# FanController_v1.net
KiCad netlist of a schematic drawn in EAGLE
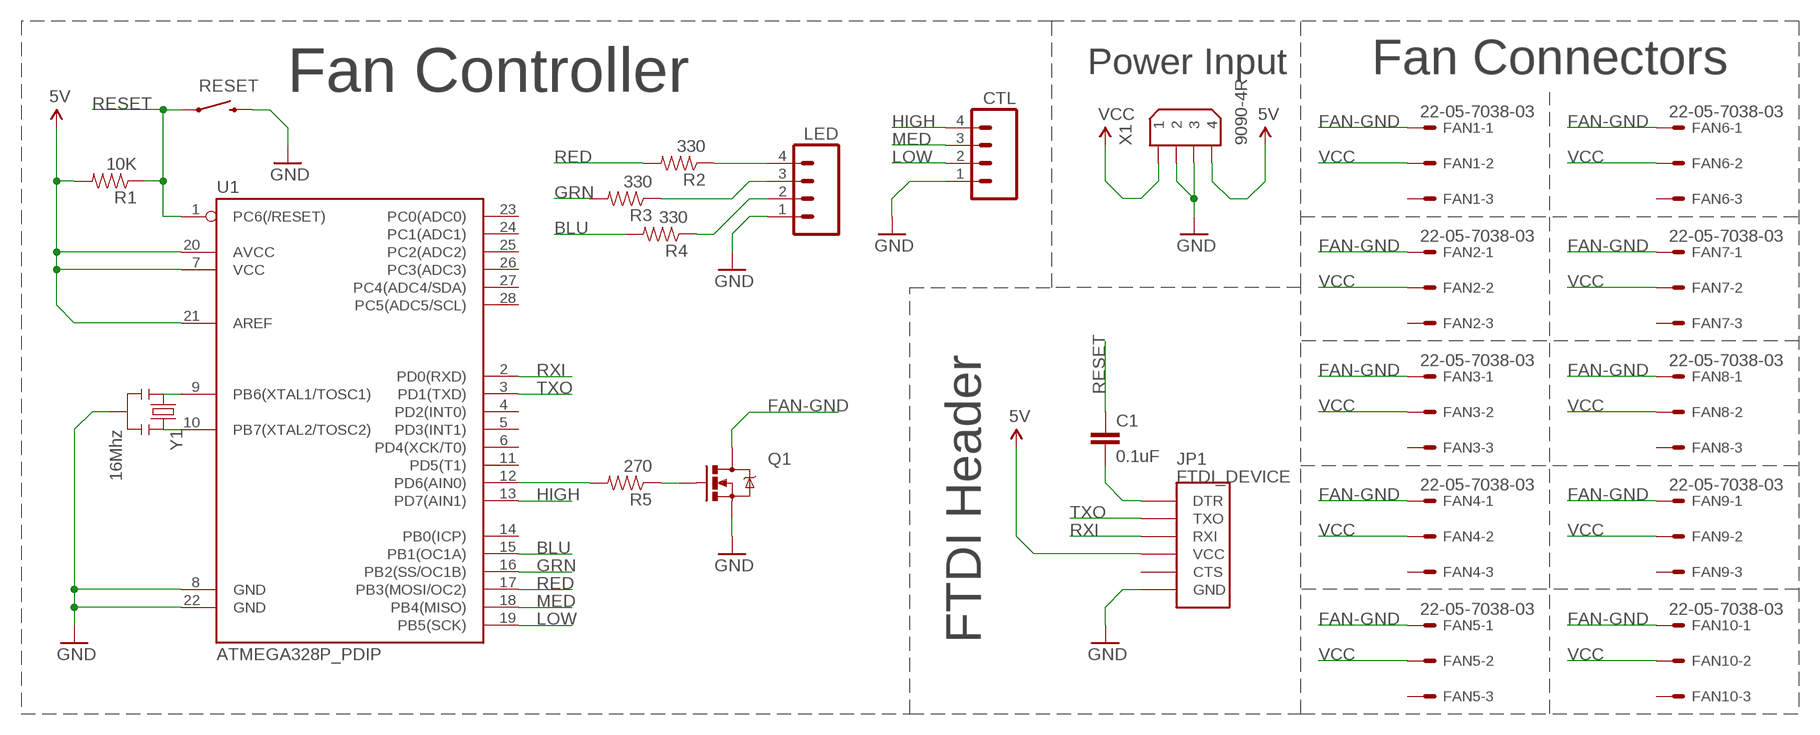
[diagram p0: schematic, sheet 1]

(export (version "E")
  (design (tool "Eeschema 10.0.6"))
  (components
    (comp (ref "C1")
      (value "0.1uF")
      (footprint "eagle-import:CAP-PTH-SMALL")
      (libsource (lib "eagle-import") (part "CAPPTH"))
    )
    (comp (ref "CTL")
      (value "M04PTH")
      (footprint "eagle-import:1X04")
      (libsource (lib "eagle-import") (part "M04PTH"))
    )
    (comp (ref "FAN1")
      (value "22-05-7038-03")
      (footprint "eagle-import:7395-03")
      (libsource (lib "eagle-import") (part "22-?-0305-7038"))
    )
    (comp (ref "FAN2")
      (value "22-05-7038-03")
      (footprint "eagle-import:7395-03")
      (libsource (lib "eagle-import") (part "22-?-0305-7038"))
    )
    (comp (ref "FAN3")
      (value "22-05-7038-03")
      (footprint "eagle-import:7395-03")
      (libsource (lib "eagle-import") (part "22-?-0305-7038"))
    )
    (comp (ref "FAN4")
      (value "22-05-7038-03")
      (footprint "eagle-import:7395-03")
      (libsource (lib "eagle-import") (part "22-?-0305-7038"))
    )
    (comp (ref "FAN5")
      (value "22-05-7038-03")
      (footprint "eagle-import:7395-03")
      (libsource (lib "eagle-import") (part "22-?-0305-7038"))
    )
    (comp (ref "FAN6")
      (value "22-05-7038-03")
      (footprint "eagle-import:7395-03")
      (libsource (lib "eagle-import") (part "22-?-0305-7038"))
    )
    (comp (ref "FAN7")
      (value "22-05-7038-03")
      (footprint "eagle-import:7395-03")
      (libsource (lib "eagle-import") (part "22-?-0305-7038"))
    )
    (comp (ref "FAN8")
      (value "22-05-7038-03")
      (footprint "eagle-import:7395-03")
      (libsource (lib "eagle-import") (part "22-?-0305-7038"))
    )
    (comp (ref "FAN9")
      (value "22-05-7038-03")
      (footprint "eagle-import:7395-03")
      (libsource (lib "eagle-import") (part "22-?-0305-7038"))
    )
    (comp (ref "FAN10")
      (value "22-05-7038-03")
      (footprint "eagle-import:7395-03")
      (libsource (lib "eagle-import") (part "22-?-0305-7038"))
    )
    (comp (ref "JP1")
      (value "FTDI_DEVICE")
      (footprint "eagle-import:FTDI_DEVICE_SIDE")
      (libsource (lib "eagle-import") (part "FTDI_DEVICE"))
    )
    (comp (ref "LED")
      (value "M04PTH")
      (footprint "eagle-import:1X04")
      (libsource (lib "eagle-import") (part "M04PTH"))
    )
    (comp (ref "Q1")
      (value "MOSFET-NCHANNELFQP30N06L")
      (footprint "eagle-import:TO220V")
      (libsource (lib "eagle-import") (part "MOSFET-NCHANNELFQP30N06L"))
    )
    (comp (ref "R1")
      (value "10K")
      (footprint "eagle-import:AXIAL-0.4")
      (libsource (lib "eagle-import") (part "RESISTORPTH-1/4W"))
    )
    (comp (ref "R2")
      (value "330")
      (footprint "eagle-import:AXIAL-0.4")
      (libsource (lib "eagle-import") (part "RESISTORPTH-1/4W"))
    )
    (comp (ref "R3")
      (value "330")
      (footprint "eagle-import:AXIAL-0.4")
      (libsource (lib "eagle-import") (part "RESISTORPTH-1/4W"))
    )
    (comp (ref "R4")
      (value "330")
      (footprint "eagle-import:AXIAL-0.4")
      (libsource (lib "eagle-import") (part "RESISTORPTH-1/4W"))
    )
    (comp (ref "R5")
      (value "270")
      (footprint "eagle-import:AXIAL-0.4")
      (libsource (lib "eagle-import") (part "RESISTORPTH-1/4W"))
    )
    (comp (ref "RESET")
      (value "SWITCH-MOMENTARY-2PTH")
      (footprint "eagle-import:TACTILE-PTH")
      (libsource (lib "eagle-import") (part "SWITCH-MOMENTARY-2PTH"))
    )
    (comp (ref "U1")
      (value "ATMEGA328P_PDIP")
      (footprint "eagle-import:DIL28-3")
      (libsource (lib "eagle-import") (part "ATMEGA328P_PDIP"))
    )
    (comp (ref "X1")
      (value "9090-4R")
      (footprint "eagle-import:9090-4R")
      (libsource (lib "eagle-import") (part "9090-4R"))
    )
    (comp (ref "Y1")
      (value "16Mhz")
      (footprint "eagle-import:RESONATOR-PTH")
      (libsource (lib "eagle-import") (part "RESONATORPTH"))
    )
  )
  (nets
    (net (code "1") (name "/BLU") (class "Default")
      (node (ref "R4") (pin "P$2") (pinfunction "2_P$2") (pintype "passive"))
      (node (ref "U1") (pin "15") (pinfunction "PB1(OC1A)_15") (pintype "bidirectional"))
    )
    (net (code "2") (name "/FAN-GND") (class "Default")
      (node (ref "FAN1") (pin "1") (pinfunction "S_1") (pintype "passive"))
      (node (ref "FAN10") (pin "1") (pinfunction "S_1") (pintype "passive"))
      (node (ref "FAN2") (pin "1") (pinfunction "S_1") (pintype "passive"))
      (node (ref "FAN3") (pin "1") (pinfunction "S_1") (pintype "passive"))
      (node (ref "FAN4") (pin "1") (pinfunction "S_1") (pintype "passive"))
      (node (ref "FAN5") (pin "1") (pinfunction "S_1") (pintype "passive"))
      (node (ref "FAN6") (pin "1") (pinfunction "S_1") (pintype "passive"))
      (node (ref "FAN7") (pin "1") (pinfunction "S_1") (pintype "passive"))
      (node (ref "FAN8") (pin "1") (pinfunction "S_1") (pintype "passive"))
      (node (ref "FAN9") (pin "1") (pinfunction "S_1") (pintype "passive"))
      (node (ref "Q1") (pin "2") (pinfunction "D_2") (pintype "passive"))
    )
    (net (code "3") (name "/GRN") (class "Default")
      (node (ref "R3") (pin "P$2") (pinfunction "2_P$2") (pintype "passive"))
      (node (ref "U1") (pin "16") (pinfunction "PB2(SS/OC1B)_16") (pintype "bidirectional"))
    )
    (net (code "4") (name "/HIGH") (class "Default")
      (node (ref "CTL") (pin "4") (pinfunction "4_4") (pintype "passive"))
      (node (ref "U1") (pin "13") (pinfunction "PD7(AIN1)_13") (pintype "bidirectional"))
    )
    (net (code "5") (name "/LOW") (class "Default")
      (node (ref "CTL") (pin "2") (pinfunction "2_2") (pintype "passive"))
      (node (ref "U1") (pin "19") (pinfunction "PB5(SCK)_19") (pintype "bidirectional"))
    )
    (net (code "6") (name "/MED") (class "Default")
      (node (ref "CTL") (pin "3") (pinfunction "3_3") (pintype "passive"))
      (node (ref "U1") (pin "18") (pinfunction "PB4(MISO)_18") (pintype "bidirectional"))
    )
    (net (code "7") (name "/RED") (class "Default")
      (node (ref "R2") (pin "P$2") (pinfunction "2_P$2") (pintype "passive"))
      (node (ref "U1") (pin "17") (pinfunction "PB3(MOSI/OC2)_17") (pintype "bidirectional"))
    )
    (net (code "8") (name "/RESET") (class "Default")
      (node (ref "C1") (pin "1") (pinfunction "1_1") (pintype "passive"))
      (node (ref "R1") (pin "P$1") (pinfunction "1_P$1") (pintype "passive"))
      (node (ref "RESET") (pin "1") (pinfunction "1_1") (pintype "passive"))
      (node (ref "U1") (pin "1") (pinfunction "PC6(/RESET)_1") (pintype "bidirectional"))
    )
    (net (code "9") (name "/RXI") (class "Default")
      (node (ref "JP1") (pin "P$3") (pinfunction "RXI_P$3") (pintype "bidirectional"))
      (node (ref "U1") (pin "2") (pinfunction "PD0(RXD)_2") (pintype "bidirectional"))
    )
    (net (code "10") (name "/TXO") (class "Default")
      (node (ref "JP1") (pin "P$2") (pinfunction "TXO_P$2") (pintype "bidirectional"))
      (node (ref "U1") (pin "3") (pinfunction "PD1(TXD)_3") (pintype "bidirectional"))
    )
    (net (code "11") (name "5V") (class "Default")
      (node (ref "JP1") (pin "P$4") (pinfunction "VCC_P$4") (pintype "bidirectional"))
      (node (ref "R1") (pin "P$2") (pinfunction "2_P$2") (pintype "passive"))
      (node (ref "U1") (pin "20") (pinfunction "AVCC_20") (pintype "bidirectional"))
      (node (ref "U1") (pin "21") (pinfunction "AREF_21") (pintype "bidirectional"))
      (node (ref "U1") (pin "7") (pinfunction "VCC_7") (pintype "bidirectional"))
      (node (ref "X1") (pin "4") (pinfunction "4_4") (pintype "passive"))
    )
    (net (code "12") (name "GND") (class "Default")
      (node (ref "CTL") (pin "1") (pinfunction "1_1") (pintype "passive"))
      (node (ref "JP1") (pin "P$6") (pinfunction "GND_P$6") (pintype "bidirectional"))
      (node (ref "LED") (pin "1") (pinfunction "1_1") (pintype "passive"))
      (node (ref "Q1") (pin "3") (pinfunction "S_3") (pintype "passive"))
      (node (ref "RESET") (pin "3") (pinfunction "2_3") (pintype "passive"))
      (node (ref "U1") (pin "22") (pinfunction "GND_22") (pintype "bidirectional"))
      (node (ref "U1") (pin "8") (pinfunction "GND_8") (pintype "bidirectional"))
      (node (ref "X1") (pin "2") (pinfunction "2_2") (pintype "passive"))
      (node (ref "X1") (pin "3") (pinfunction "3_3") (pintype "passive"))
      (node (ref "Y1") (pin "2") (pinfunction "2_2") (pintype "passive"))
    )
    (net (code "13") (name "Net-(JP1-DTR)") (class "Default")
      (node (ref "C1") (pin "2") (pinfunction "2_2") (pintype "passive"))
      (node (ref "JP1") (pin "P$1") (pinfunction "DTR_P$1") (pintype "bidirectional"))
    )
    (net (code "14") (name "Net-(Q1-G)") (class "Default")
      (node (ref "Q1") (pin "1") (pinfunction "G_1") (pintype "passive"))
      (node (ref "R5") (pin "P$1") (pinfunction "1_P$1") (pintype "passive"))
    )
    (net (code "15") (name "Net-(R2-1)") (class "Default")
      (node (ref "LED") (pin "4") (pinfunction "4_4") (pintype "passive"))
      (node (ref "R2") (pin "P$1") (pinfunction "1_P$1") (pintype "passive"))
    )
    (net (code "16") (name "Net-(R3-1)") (class "Default")
      (node (ref "LED") (pin "3") (pinfunction "3_3") (pintype "passive"))
      (node (ref "R3") (pin "P$1") (pinfunction "1_P$1") (pintype "passive"))
    )
    (net (code "17") (name "Net-(R4-1)") (class "Default")
      (node (ref "LED") (pin "2") (pinfunction "2_2") (pintype "passive"))
      (node (ref "R4") (pin "P$1") (pinfunction "1_P$1") (pintype "passive"))
    )
    (net (code "18") (name "Net-(R5-2)") (class "Default")
      (node (ref "R5") (pin "P$2") (pinfunction "2_P$2") (pintype "passive"))
      (node (ref "U1") (pin "12") (pinfunction "PD6(AIN0)_12") (pintype "bidirectional"))
    )
    (net (code "19") (name "Net-(U1-PB6(XTAL1{slash}TOSC1))") (class "Default")
      (node (ref "U1") (pin "9") (pinfunction "PB6(XTAL1/TOSC1)_9") (pintype "bidirectional"))
      (node (ref "Y1") (pin "1") (pinfunction "1_1") (pintype "passive"))
    )
    (net (code "20") (name "Net-(U1-PB7(XTAL2{slash}TOSC2))") (class "Default")
      (node (ref "U1") (pin "10") (pinfunction "PB7(XTAL2/TOSC2)_10") (pintype "bidirectional"))
      (node (ref "Y1") (pin "3") (pinfunction "3_3") (pintype "passive"))
    )
    (net (code "21") (name "VCC") (class "Default")
      (node (ref "FAN1") (pin "2") (pinfunction "S_2") (pintype "passive"))
      (node (ref "FAN10") (pin "2") (pinfunction "S_2") (pintype "passive"))
      (node (ref "FAN2") (pin "2") (pinfunction "S_2") (pintype "passive"))
      (node (ref "FAN3") (pin "2") (pinfunction "S_2") (pintype "passive"))
      (node (ref "FAN4") (pin "2") (pinfunction "S_2") (pintype "passive"))
      (node (ref "FAN5") (pin "2") (pinfunction "S_2") (pintype "passive"))
      (node (ref "FAN6") (pin "2") (pinfunction "S_2") (pintype "passive"))
      (node (ref "FAN7") (pin "2") (pinfunction "S_2") (pintype "passive"))
      (node (ref "FAN8") (pin "2") (pinfunction "S_2") (pintype "passive"))
      (node (ref "FAN9") (pin "2") (pinfunction "S_2") (pintype "passive"))
      (node (ref "X1") (pin "1") (pinfunction "1_1") (pintype "passive"))
    )
    (net (code "22") (name "unconnected-(FAN1C-S-Pad3)") (class "Default")
      (node (ref "FAN1") (pin "3") (pinfunction "S_3") (pintype "passive"))
    )
    (net (code "23") (name "unconnected-(FAN2C-S-Pad3)") (class "Default")
      (node (ref "FAN2") (pin "3") (pinfunction "S_3") (pintype "passive"))
    )
    (net (code "24") (name "unconnected-(FAN3C-S-Pad3)") (class "Default")
      (node (ref "FAN3") (pin "3") (pinfunction "S_3") (pintype "passive"))
    )
    (net (code "25") (name "unconnected-(FAN4C-S-Pad3)") (class "Default")
      (node (ref "FAN4") (pin "3") (pinfunction "S_3") (pintype "passive"))
    )
    (net (code "26") (name "unconnected-(FAN5C-S-Pad3)") (class "Default")
      (node (ref "FAN5") (pin "3") (pinfunction "S_3") (pintype "passive"))
    )
    (net (code "27") (name "unconnected-(FAN6C-S-Pad3)") (class "Default")
      (node (ref "FAN6") (pin "3") (pinfunction "S_3") (pintype "passive"))
    )
    (net (code "28") (name "unconnected-(FAN7C-S-Pad3)") (class "Default")
      (node (ref "FAN7") (pin "3") (pinfunction "S_3") (pintype "passive"))
    )
    (net (code "29") (name "unconnected-(FAN8C-S-Pad3)") (class "Default")
      (node (ref "FAN8") (pin "3") (pinfunction "S_3") (pintype "passive"))
    )
    (net (code "30") (name "unconnected-(FAN9C-S-Pad3)") (class "Default")
      (node (ref "FAN9") (pin "3") (pinfunction "S_3") (pintype "passive"))
    )
    (net (code "31") (name "unconnected-(FAN10C-S-Pad3)") (class "Default")
      (node (ref "FAN10") (pin "3") (pinfunction "S_3") (pintype "passive"))
    )
    (net (code "32") (name "unconnected-(JP1-CTS-PadP$5)") (class "Default")
      (node (ref "JP1") (pin "P$5") (pinfunction "CTS_P$5") (pintype "bidirectional"))
    )
    (net (code "33") (name "unconnected-(U1-PB0(ICP)-Pad14)") (class "Default")
      (node (ref "U1") (pin "14") (pinfunction "PB0(ICP)_14") (pintype "bidirectional"))
    )
    (net (code "34") (name "unconnected-(U1-PC0(ADC0)-Pad23)") (class "Default")
      (node (ref "U1") (pin "23") (pinfunction "PC0(ADC0)_23") (pintype "bidirectional"))
    )
    (net (code "35") (name "unconnected-(U1-PC1(ADC1)-Pad24)") (class "Default")
      (node (ref "U1") (pin "24") (pinfunction "PC1(ADC1)_24") (pintype "bidirectional"))
    )
    (net (code "36") (name "unconnected-(U1-PC2(ADC2)-Pad25)") (class "Default")
      (node (ref "U1") (pin "25") (pinfunction "PC2(ADC2)_25") (pintype "bidirectional"))
    )
    (net (code "37") (name "unconnected-(U1-PC3(ADC3)-Pad26)") (class "Default")
      (node (ref "U1") (pin "26") (pinfunction "PC3(ADC3)_26") (pintype "bidirectional"))
    )
    (net (code "38") (name "unconnected-(U1-PC4(ADC4{slash}SDA)-Pad27)") (class "Default")
      (node (ref "U1") (pin "27") (pinfunction "PC4(ADC4/SDA)_27") (pintype "bidirectional"))
    )
    (net (code "39") (name "unconnected-(U1-PC5(ADC5{slash}SCL)-Pad28)") (class "Default")
      (node (ref "U1") (pin "28") (pinfunction "PC5(ADC5/SCL)_28") (pintype "bidirectional"))
    )
    (net (code "40") (name "unconnected-(U1-PD2(INT0)-Pad4)") (class "Default")
      (node (ref "U1") (pin "4") (pinfunction "PD2(INT0)_4") (pintype "bidirectional"))
    )
    (net (code "41") (name "unconnected-(U1-PD3(INT1)-Pad5)") (class "Default")
      (node (ref "U1") (pin "5") (pinfunction "PD3(INT1)_5") (pintype "bidirectional"))
    )
    (net (code "42") (name "unconnected-(U1-PD4(XCK{slash}T0)-Pad6)") (class "Default")
      (node (ref "U1") (pin "6") (pinfunction "PD4(XCK/T0)_6") (pintype "bidirectional"))
    )
    (net (code "43") (name "unconnected-(U1-PD5(T1)-Pad11)") (class "Default")
      (node (ref "U1") (pin "11") (pinfunction "PD5(T1)_11") (pintype "bidirectional"))
    )
  )
)
